# Hx711_schematic.net
KiCad netlist of a schematic drawn in EAGLE
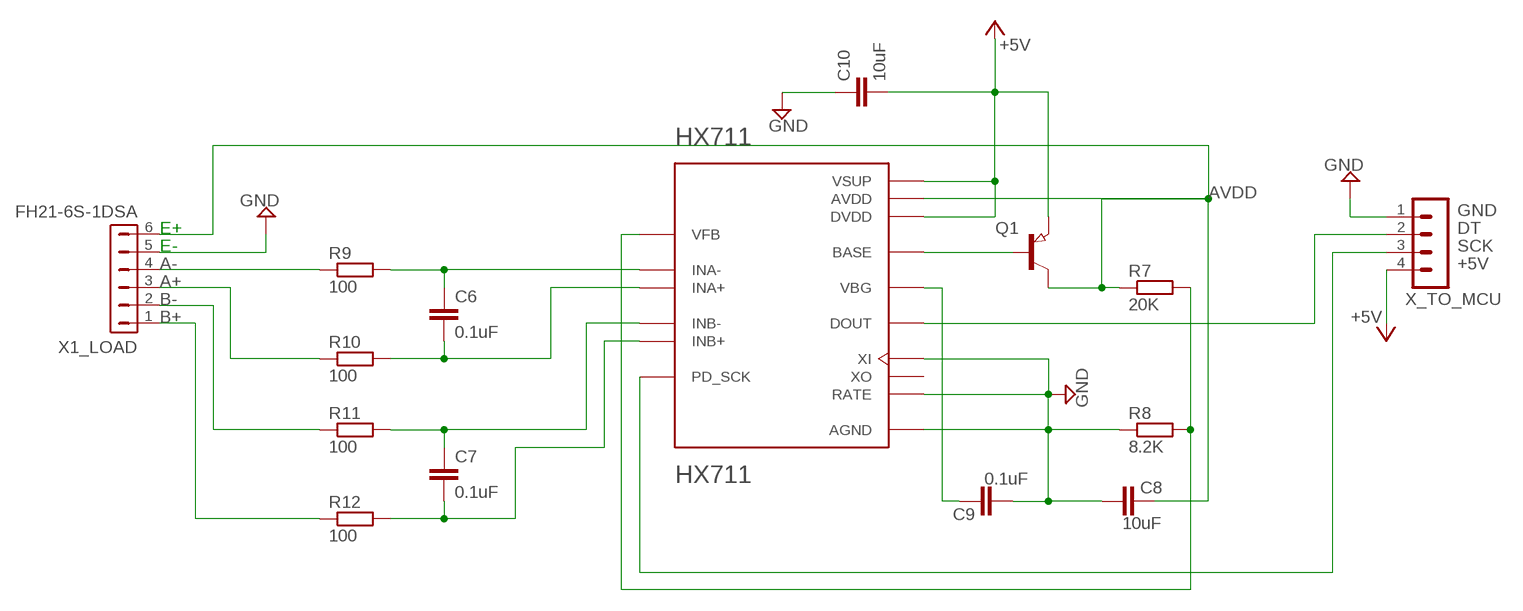
[diagram p0: schematic, sheet 1]

(export (version "E")
  (design (tool "Eeschema 10.0.6"))
  (components
    (comp (ref "C6")
      (value "0.1uF")
      (footprint "eagle-import:C2.5-2")
      (libsource (lib "eagle-import") (part "C2.5/2"))
    )
    (comp (ref "C7")
      (value "0.1uF")
      (footprint "eagle-import:C2.5-2")
      (libsource (lib "eagle-import") (part "C2.5/2"))
    )
    (comp (ref "C8")
      (value "10uF")
      (footprint "eagle-import:C2.5-2")
      (libsource (lib "eagle-import") (part "C2.5/2"))
    )
    (comp (ref "C9")
      (value "0.1uF")
      (footprint "eagle-import:C2.5-2")
      (libsource (lib "eagle-import") (part "C2.5/2"))
    )
    (comp (ref "C10")
      (value "10uF")
      (footprint "eagle-import:C2.5-2")
      (libsource (lib "eagle-import") (part "C2.5/2"))
    )
    (comp (ref "HX711")
      (value "HX711")
      (footprint "eagle-import:SOP127P600X180-16N")
      (fields (field (name "MF") "AVIA SEMICONDUCTOR"))
      (libsource (lib "eagle-import") (part "HX711"))
    )
    (comp (ref "Q1")
      (value "PNP-TRANSISTOR_SOT23")
      (footprint "eagle-import:SOT23")
      (libsource (lib "eagle-import") (part "PNP-TRANSISTOR_SOT23"))
    )
    (comp (ref "R7")
      (value "20K")
      (footprint "eagle-import:R0603")
      (libsource (lib "eagle-import") (part "R-EU_R0603"))
    )
    (comp (ref "R8")
      (value "8.2K")
      (footprint "eagle-import:R0603")
      (libsource (lib "eagle-import") (part "R-EU_R0603"))
    )
    (comp (ref "R9")
      (value "100")
      (footprint "eagle-import:R0603")
      (libsource (lib "eagle-import") (part "R-EU_R0603"))
    )
    (comp (ref "R10")
      (value "100")
      (footprint "eagle-import:R0603")
      (libsource (lib "eagle-import") (part "R-EU_R0603"))
    )
    (comp (ref "R11")
      (value "100")
      (footprint "eagle-import:R0603")
      (libsource (lib "eagle-import") (part "R-EU_R0603"))
    )
    (comp (ref "R12")
      (value "100")
      (footprint "eagle-import:R0603")
      (libsource (lib "eagle-import") (part "R-EU_R0603"))
    )
    (comp (ref "X1_LOAD")
      (value "FH21-6S-1DSA")
      (footprint "eagle-import:FH21-6S-1DSA")
      (libsource (lib "eagle-import") (part "FH21-6S-1DSA"))
    )
    (comp (ref "X_TO_MCU")
      (value "MA04-1")
      (footprint "eagle-import:MA04-1")
      (libsource (lib "eagle-import") (part "MA04-1"))
    )
  )
  (nets
    (net (code "1") (name "+5V") (class "Default")
      (node (ref "C10") (pin "2") (pinfunction "2_2") (pintype "passive"))
      (node (ref "HX711") (pin "1") (pinfunction "VSUP_1") (pintype "power_in"))
      (node (ref "HX711") (pin "16") (pinfunction "DVDD_16") (pintype "power_in"))
      (node (ref "Q1") (pin "2") (pinfunction "E_2") (pintype "passive"))
      (node (ref "X_TO_MCU") (pin "4") (pinfunction "4_4") (pintype "passive"))
    )
    (net (code "2") (name "/A+") (class "Default")
      (node (ref "R10") (pin "1") (pinfunction "1_1") (pintype "passive"))
      (node (ref "X1_LOAD") (pin "3") (pinfunction "3_3") (pintype "passive"))
    )
    (net (code "3") (name "/A-") (class "Default")
      (node (ref "R9") (pin "1") (pinfunction "1_1") (pintype "passive"))
      (node (ref "X1_LOAD") (pin "4") (pinfunction "4_4") (pintype "passive"))
    )
    (net (code "4") (name "/AVDD") (class "Default")
      (node (ref "C8") (pin "1") (pinfunction "1_1") (pintype "passive"))
      (node (ref "HX711") (pin "3") (pinfunction "AVDD_3") (pintype "power_in"))
      (node (ref "Q1") (pin "3") (pinfunction "C_3") (pintype "passive"))
      (node (ref "R7") (pin "1") (pinfunction "1_1") (pintype "passive"))
      (node (ref "X1_LOAD") (pin "6") (pinfunction "6_6") (pintype "passive"))
    )
    (net (code "5") (name "/B+") (class "Default")
      (node (ref "R12") (pin "1") (pinfunction "1_1") (pintype "passive"))
      (node (ref "X1_LOAD") (pin "1") (pinfunction "1_1") (pintype "passive"))
    )
    (net (code "6") (name "/B-") (class "Default")
      (node (ref "R11") (pin "1") (pinfunction "1_1") (pintype "passive"))
      (node (ref "X1_LOAD") (pin "2") (pinfunction "2_2") (pintype "passive"))
    )
    (net (code "7") (name "/DT") (class "Default")
      (node (ref "HX711") (pin "12") (pinfunction "DOUT_12") (pintype "output"))
      (node (ref "X_TO_MCU") (pin "2") (pinfunction "2_2") (pintype "passive"))
    )
    (net (code "8") (name "/SCK") (class "Default")
      (node (ref "HX711") (pin "11") (pinfunction "PD_SCK_11") (pintype "input"))
      (node (ref "X_TO_MCU") (pin "3") (pinfunction "3_3") (pintype "passive"))
    )
    (net (code "9") (name "GND") (class "Default")
      (node (ref "C10") (pin "1") (pinfunction "1_1") (pintype "passive"))
      (node (ref "C8") (pin "2") (pinfunction "2_2") (pintype "passive"))
      (node (ref "C9") (pin "2") (pinfunction "2_2") (pintype "passive"))
      (node (ref "HX711") (pin "14") (pinfunction "XI_14") (pintype "input"))
      (node (ref "HX711") (pin "15") (pinfunction "RATE_15") (pintype "input"))
      (node (ref "HX711") (pin "5") (pinfunction "AGND_5") (pintype "power_in"))
      (node (ref "R8") (pin "1") (pinfunction "1_1") (pintype "passive"))
      (node (ref "X1_LOAD") (pin "5") (pinfunction "5_5") (pintype "passive"))
      (node (ref "X_TO_MCU") (pin "1") (pinfunction "1_1") (pintype "passive"))
    )
    (net (code "10") (name "Net-(HX711-BASE)") (class "Default")
      (node (ref "HX711") (pin "2") (pinfunction "BASE_2") (pintype "output"))
      (node (ref "Q1") (pin "1") (pinfunction "B_1") (pintype "passive"))
    )
    (net (code "11") (name "Net-(HX711-INA+)") (class "Default")
      (node (ref "C6") (pin "2") (pinfunction "2_2") (pintype "passive"))
      (node (ref "HX711") (pin "8") (pinfunction "INA+_8") (pintype "input"))
      (node (ref "R10") (pin "2") (pinfunction "2_2") (pintype "passive"))
    )
    (net (code "12") (name "Net-(HX711-INA-)") (class "Default")
      (node (ref "C6") (pin "1") (pinfunction "1_1") (pintype "passive"))
      (node (ref "HX711") (pin "7") (pinfunction "INA-_7") (pintype "input"))
      (node (ref "R9") (pin "2") (pinfunction "2_2") (pintype "passive"))
    )
    (net (code "13") (name "Net-(HX711-INB+)") (class "Default")
      (node (ref "C7") (pin "2") (pinfunction "2_2") (pintype "passive"))
      (node (ref "HX711") (pin "10") (pinfunction "INB+_10") (pintype "input"))
      (node (ref "R12") (pin "2") (pinfunction "2_2") (pintype "passive"))
    )
    (net (code "14") (name "Net-(HX711-INB-)") (class "Default")
      (node (ref "C7") (pin "1") (pinfunction "1_1") (pintype "passive"))
      (node (ref "HX711") (pin "9") (pinfunction "INB-_9") (pintype "input"))
      (node (ref "R11") (pin "2") (pinfunction "2_2") (pintype "passive"))
    )
    (net (code "15") (name "Net-(HX711-VBG)") (class "Default")
      (node (ref "C9") (pin "1") (pinfunction "1_1") (pintype "passive"))
      (node (ref "HX711") (pin "6") (pinfunction "VBG_6") (pintype "output"))
    )
    (net (code "16") (name "Net-(HX711-VFB)") (class "Default")
      (node (ref "HX711") (pin "4") (pinfunction "VFB_4") (pintype "input"))
      (node (ref "R7") (pin "2") (pinfunction "2_2") (pintype "passive"))
      (node (ref "R8") (pin "2") (pinfunction "2_2") (pintype "passive"))
    )
    (net (code "17") (name "unconnected-(HX711-XO-Pad13)") (class "Default")
      (node (ref "HX711") (pin "13") (pinfunction "XO_13") (pintype "output"))
    )
  )
)
